# MainMCU.net
KiCad netlist of a schematic drawn in Altium Designer
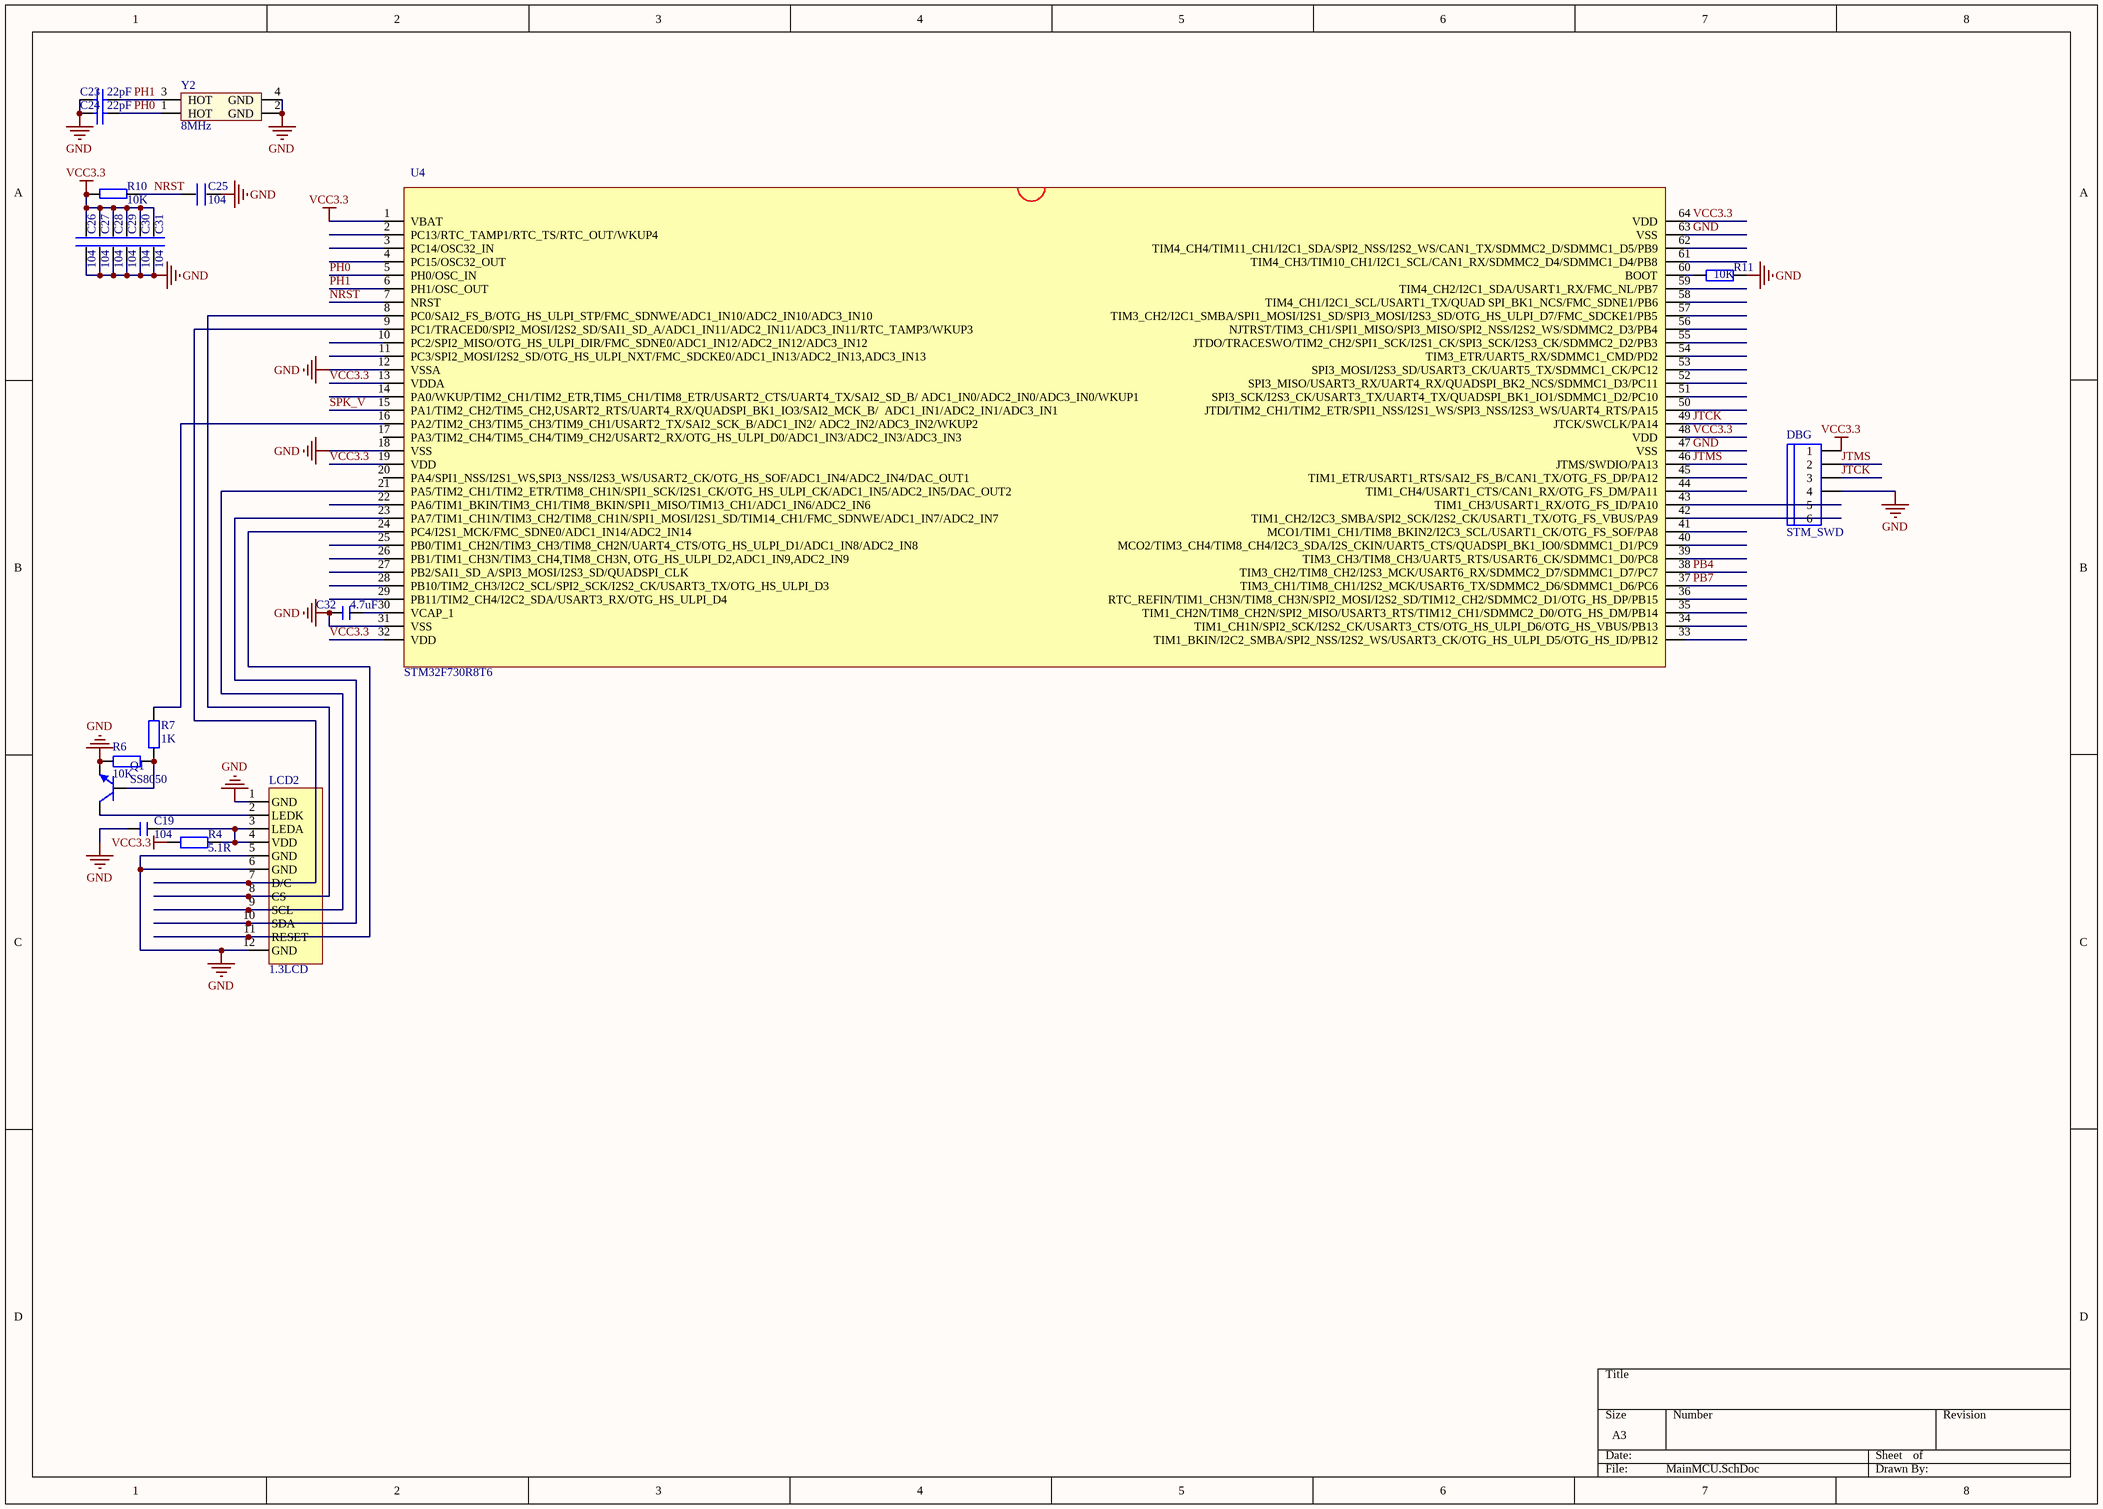
[diagram p0: MainMCU.SchDoc]

(export (version "E")
  (design (tool "Eeschema 10.0.6"))
  (components
    (comp (ref "C19")
      (value "104")
      (footprint "C 0603_L")
      (description "无极性电容")
      (fields (field (name "版权归属") "正点原子"))
      (libsource (lib "正点原子封装库V1.0") (part "C"))
    )
    (comp (ref "C23") (value "22pF") (footprint "C 0603_L") (libsource (lib "L476") (part "CAP")))
    (comp (ref "C24") (value "22pF") (footprint "C 0603_L") (libsource (lib "L476") (part "CAP")))
    (comp (ref "C25")
      (value "104")
      (footprint "C 0603_L")
      (libsource (lib "IMX6UL_ALPHA(底板)_V2.0") (part "C"))
    )
    (comp (ref "C26")
      (value "104")
      (footprint "C 0603_L")
      (libsource (lib "IMX6UL_ALPHA(底板)_V2.0") (part "C"))
    )
    (comp (ref "C27")
      (value "104")
      (footprint "C 0603_L")
      (libsource (lib "IMX6UL_ALPHA(底板)_V2.0") (part "C"))
    )
    (comp (ref "C28")
      (value "104")
      (footprint "C 0603_L")
      (libsource (lib "IMX6UL_ALPHA(底板)_V2.0") (part "C"))
    )
    (comp (ref "C29")
      (value "104")
      (footprint "C 0603_L")
      (libsource (lib "IMX6UL_ALPHA(底板)_V2.0") (part "C"))
    )
    (comp (ref "C30")
      (value "104")
      (footprint "C 0603_L")
      (libsource (lib "IMX6UL_ALPHA(底板)_V2.0") (part "C"))
    )
    (comp (ref "C31")
      (value "104")
      (footprint "C 0603_L")
      (libsource (lib "IMX6UL_ALPHA(底板)_V2.0") (part "C"))
    )
    (comp (ref "C32")
      (value "4.7uF")
      (footprint "C 0603_L")
      (description "无极性贴片电容")
      (fields (field (name "版权归属") "源创客"))
      (libsource (lib "电阻-电容-电感") (part "C"))
    )
    (comp (ref "DBG")
      (value "STM_SWD")
      (footprint "SH1.0 S-W-6P")
      (libsource (lib "MiniFly ") (part "HEAD6"))
    )
    (comp (ref "LCD2")
      (value "1.3LCD")
      (footprint "TFT-N133-2424THBIG01")
      (description "TFTLCD,240*240,SPI")
      (libsource (lib "ATK-MD0130 V2.0") (part "TFTLCD-N133-2424THBIG01"))
    )
    (comp (ref "Q1")
      (value "SS8050")
      (footprint "SOT23-3L")
      (description "高频放大-NPN型")
      (fields (field (name "版权归属") "正点原子"))
      (libsource (lib "正点原子封装库V1.0") (part "8050-SMD"))
    )
    (comp (ref "R4")
      (value "5.1R")
      (footprint "R 0805_L")
      (description "贴片电阻")
      (libsource (lib "LovelessingSch") (part "R"))
    )
    (comp (ref "R6")
      (value "10K")
      (footprint "R 0603_L")
      (description "贴片电阻")
      (libsource (lib "LovelessingSch") (part "R"))
    )
    (comp (ref "R7")
      (value "1K")
      (footprint "R 0603_L")
      (description "贴片电阻")
      (libsource (lib "LovelessingSch") (part "R"))
    )
    (comp (ref "R10")
      (value "10K")
      (footprint "R 0603_L")
      (libsource (lib "IMX6UL_ALPHA(底板)_V2.0") (part "R"))
    )
    (comp (ref "R11")
      (value "10K")
      (footprint "R 0603_L")
      (description "贴片电阻")
      (fields (field (name "版权归属") "源创客"))
      (libsource (lib "电阻-电容-电感") (part "R"))
    )
    (comp (ref "U4")
      (value "STM32F730R8T6")
      (footprint "LQFP64 10x10_L")
      (description "STM32 M7内核")
      (libsource (lib "fantasylib") (part "STM32F730R8T6"))
    )
    (comp (ref "Y2")
      (value "8MHz")
      (footprint "OSC 3225-4P")
      (description "晶振25MHz")
      (fields (field (name "PUBLISHER") "Altium Limited"))
      (libsource (lib "LovelessingSch") (part "Y-3225-4P"))
    )
  )
  (nets
    (net (code "1") (name "/JTCK") (class "Default")
      (node (ref "DBG") (pin "3") (pinfunction "3_3") (pintype "passive"))
      (node (ref "U4") (pin "49") (pinfunction "JTCK/SWCLK/PA14_49") (pintype "passive"))
    )
    (net (code "2") (name "/JTMS") (class "Default")
      (node (ref "DBG") (pin "2") (pinfunction "2_2") (pintype "passive"))
      (node (ref "U4") (pin "46") (pinfunction "JTMS/SWDIO/PA13_46") (pintype "passive"))
    )
    (net (code "3") (name "/NRST") (class "Default")
      (node (ref "C25") (pin "2") (pintype "passive"))
      (node (ref "R10") (pin "1") (pintype "passive"))
      (node (ref "U4") (pin "7") (pinfunction "NRST_7") (pintype "passive"))
    )
    (net (code "4") (name "/PB4") (class "Default")
      (node (ref "U4") (pin "38") (pinfunction "TIM3_CH2/TIM8_CH2/I2S3_MCK/USART6_RX/SDMMC2_D7/SDMMC1_D7/PC7_38") (pintype "passive"))
    )
    (net (code "5") (name "/PB7") (class "Default")
      (node (ref "U4") (pin "37") (pinfunction "TIM3_CH1/TIM8_CH1/I2S2_MCK/USART6_TX/SDMMC2_D6/SDMMC1_D6/PC6_37") (pintype "passive"))
    )
    (net (code "6") (name "/PH0") (class "Default")
      (node (ref "C24") (pin "1") (pinfunction "1_1") (pintype "passive"))
      (node (ref "U4") (pin "5") (pinfunction "PH0/OSC_IN_5") (pintype "passive"))
      (node (ref "Y2") (pin "1") (pinfunction "HOT_1") (pintype "passive"))
    )
    (net (code "7") (name "/PH1") (class "Default")
      (node (ref "C23") (pin "1") (pinfunction "1_1") (pintype "passive"))
      (node (ref "U4") (pin "6") (pinfunction "PH1/OSC_OUT_6") (pintype "passive"))
      (node (ref "Y2") (pin "3") (pinfunction "HOT_3") (pintype "passive"))
    )
    (net (code "8") (name "/SPK_V") (class "Default")
      (node (ref "U4") (pin "15") (pinfunction "PA1/TIM2_CH2/TIM5_CH2,USART2_RTS/UART4_RX/QUADSPI_BK1_IO3/SAI2_MCK_B/__ADC1_IN1/ADC2_IN1/ADC3_IN1_15") (pintype "passive"))
    )
    (net (code "9") (name "GND") (class "Default")
      (node (ref "C19") (pin "2") (pinfunction "2_2") (pintype "passive"))
      (node (ref "C23") (pin "2") (pinfunction "2_2") (pintype "passive"))
      (node (ref "C24") (pin "2") (pinfunction "2_2") (pintype "passive"))
      (node (ref "C25") (pin "1") (pintype "passive"))
      (node (ref "C26") (pin "2") (pintype "passive"))
      (node (ref "C27") (pin "2") (pintype "passive"))
      (node (ref "C28") (pin "2") (pintype "passive"))
      (node (ref "C29") (pin "2") (pintype "passive"))
      (node (ref "C30") (pin "2") (pintype "passive"))
      (node (ref "C31") (pin "2") (pintype "passive"))
      (node (ref "C32") (pin "1") (pinfunction "1_1") (pintype "passive"))
      (node (ref "DBG") (pin "4") (pinfunction "4_4") (pintype "passive"))
      (node (ref "LCD2") (pin "1") (pinfunction "GND_1") (pintype "passive"))
      (node (ref "LCD2") (pin "12") (pinfunction "GND_12") (pintype "passive"))
      (node (ref "LCD2") (pin "5") (pinfunction "GND_5") (pintype "passive"))
      (node (ref "LCD2") (pin "6") (pinfunction "GND_6") (pintype "passive"))
      (node (ref "Q1") (pin "2") (pinfunction "E_2") (pintype "passive"))
      (node (ref "R11") (pin "1") (pinfunction "1_1") (pintype "passive"))
      (node (ref "R6") (pin "2") (pinfunction "2_2") (pintype "passive"))
      (node (ref "U4") (pin "12") (pinfunction "VSSA_12") (pintype "passive"))
      (node (ref "U4") (pin "18") (pinfunction "VSS_18") (pintype "passive"))
      (node (ref "U4") (pin "31") (pinfunction "VSS_31") (pintype "passive"))
      (node (ref "U4") (pin "47") (pinfunction "VSS_47") (pintype "passive"))
      (node (ref "U4") (pin "63") (pinfunction "VSS_63") (pintype "passive"))
      (node (ref "Y2") (pin "2") (pinfunction "GND_2") (pintype "passive"))
      (node (ref "Y2") (pin "4") (pinfunction "GND_4") (pintype "passive"))
    )
    (net (code "10") (name "Net-(LCD2-CS)") (class "Default")
      (node (ref "LCD2") (pin "8") (pinfunction "CS_8") (pintype "passive"))
      (node (ref "U4") (pin "8") (pinfunction "PC0/SAI2_FS_B/OTG_HS_ULPI_STP/FMC_SDNWE/ADC1_IN10/ADC2_IN10/ADC3_IN10_8") (pintype "passive"))
    )
    (net (code "11") (name "Net-(LCD2-D{slash}C)") (class "Default")
      (node (ref "LCD2") (pin "7") (pinfunction "D/C_7") (pintype "passive"))
      (node (ref "U4") (pin "9") (pinfunction "PC1/TRACED0/SPI2_MOSI/I2S2_SD/SAI1_SD_A/ADC1_IN11/ADC2_IN11/ADC3_IN11/RTC_TAMP3/WKUP3_9") (pintype "passive"))
    )
    (net (code "12") (name "Net-(LCD2-LEDA)") (class "Default")
      (node (ref "C19") (pin "1") (pinfunction "1_1") (pintype "passive"))
      (node (ref "LCD2") (pin "3") (pinfunction "LEDA_3") (pintype "passive"))
      (node (ref "LCD2") (pin "4") (pinfunction "VDD_4") (pintype "passive"))
      (node (ref "R4") (pin "2") (pinfunction "2_2") (pintype "passive"))
    )
    (net (code "13") (name "Net-(LCD2-LEDK)") (class "Default")
      (node (ref "LCD2") (pin "2") (pinfunction "LEDK_2") (pintype "passive"))
      (node (ref "Q1") (pin "3") (pinfunction "C_3") (pintype "passive"))
    )
    (net (code "14") (name "Net-(LCD2-RESET)") (class "Default")
      (node (ref "LCD2") (pin "11") (pinfunction "RESET_11") (pintype "passive"))
      (node (ref "U4") (pin "24") (pinfunction "PC4/I2S1_MCK/FMC_SDNE0/ADC1_IN14/ADC2_IN14_24") (pintype "passive"))
    )
    (net (code "15") (name "Net-(LCD2-SCL)") (class "Default")
      (node (ref "LCD2") (pin "9") (pinfunction "SCL_9") (pintype "passive"))
      (node (ref "U4") (pin "21") (pinfunction "PA5/TIM2_CH1/TIM2_ETR/TIM8_CH1N/SPI1_SCK/I2S1_CK/OTG_HS_ULPI_CK/ADC1_IN5/ADC2_IN5/DAC_OUT2_21") (pintype "passive"))
    )
    (net (code "16") (name "Net-(LCD2-SDA)") (class "Default")
      (node (ref "LCD2") (pin "10") (pinfunction "SDA_10") (pintype "passive"))
      (node (ref "U4") (pin "23") (pinfunction "PA7/TIM1_CH1N/TIM3_CH2/TIM8_CH1N/SPI1_MOSI/I2S1_SD/TIM14_CH1/FMC_SDNWE/ADC1_IN7/ADC2_IN7_23") (pintype "passive"))
    )
    (net (code "17") (name "Net-(Q1-B)") (class "Default")
      (node (ref "Q1") (pin "1") (pinfunction "B_1") (pintype "passive"))
      (node (ref "R6") (pin "1") (pinfunction "1_1") (pintype "passive"))
      (node (ref "R7") (pin "2") (pinfunction "2_2") (pintype "passive"))
    )
    (net (code "18") (name "Net-(U4-BOOT)") (class "Default")
      (node (ref "R11") (pin "2") (pinfunction "2_2") (pintype "passive"))
      (node (ref "U4") (pin "60") (pinfunction "BOOT_60") (pintype "passive"))
    )
    (net (code "19") (name "Net-(U4-PA2{slash}TIM2_CH3{slash}TIM5_CH3{slash}TIM9_CH1{slash}USART2_TX{slash}SAI2_SCK_B{slash}ADC1_IN2{slash}_ADC2_IN2{slash}ADC3_IN2{slash}WKUP2)") (class "Default")
      (node (ref "R7") (pin "1") (pinfunction "1_1") (pintype "passive"))
      (node (ref "U4") (pin "16") (pinfunction "PA2/TIM2_CH3/TIM5_CH3/TIM9_CH1/USART2_TX/SAI2_SCK_B/ADC1_IN2/_ADC2_IN2/ADC3_IN2/WKUP2_16") (pintype "passive"))
    )
    (net (code "20") (name "Net-(U4-TIM1_CH2{slash}I2C3_SMBA{slash}SPI2_SCK{slash}I2S2_CK{slash}USART1_TX{slash}OTG_FS_VBUS{slash}PA9)") (class "Default")
      (node (ref "DBG") (pin "6") (pinfunction "6_6") (pintype "passive"))
      (node (ref "U4") (pin "42") (pinfunction "TIM1_CH2/I2C3_SMBA/SPI2_SCK/I2S2_CK/USART1_TX/OTG_FS_VBUS/PA9_42") (pintype "passive"))
    )
    (net (code "21") (name "Net-(U4-TIM1_CH3{slash}USART1_RX{slash}OTG_FS_ID{slash}PA10)") (class "Default")
      (node (ref "DBG") (pin "5") (pinfunction "5_5") (pintype "passive"))
      (node (ref "U4") (pin "43") (pinfunction "TIM1_CH3/USART1_RX/OTG_FS_ID/PA10_43") (pintype "passive"))
    )
    (net (code "22") (name "Net-(U4-VCAP_1)") (class "Default")
      (node (ref "C32") (pin "2") (pinfunction "2_2") (pintype "passive"))
      (node (ref "U4") (pin "30") (pinfunction "VCAP_1_30") (pintype "passive"))
    )
    (net (code "23") (name "VCC3.3") (class "Default")
      (node (ref "C26") (pin "1") (pintype "passive"))
      (node (ref "C27") (pin "1") (pintype "passive"))
      (node (ref "C28") (pin "1") (pintype "passive"))
      (node (ref "C29") (pin "1") (pintype "passive"))
      (node (ref "C30") (pin "1") (pintype "passive"))
      (node (ref "C31") (pin "1") (pintype "passive"))
      (node (ref "DBG") (pin "1") (pinfunction "1_1") (pintype "passive"))
      (node (ref "R10") (pin "2") (pintype "passive"))
      (node (ref "R4") (pin "1") (pinfunction "1_1") (pintype "passive"))
      (node (ref "U4") (pin "1") (pinfunction "VBAT_1") (pintype "passive"))
      (node (ref "U4") (pin "13") (pinfunction "VDDA_13") (pintype "passive"))
      (node (ref "U4") (pin "19") (pinfunction "VDD_19") (pintype "passive"))
      (node (ref "U4") (pin "32") (pinfunction "VDD_32") (pintype "passive"))
      (node (ref "U4") (pin "48") (pinfunction "VDD_48") (pintype "passive"))
      (node (ref "U4") (pin "64") (pinfunction "VDD_64") (pintype "passive"))
    )
    (net (code "24") (name "unconnected-(U4-JTDI{slash}TIM2_CH1{slash}TIM2_ETR{slash}SPI1_NSS{slash}I2S1_WS{slash}SPI3_NSS{slash}I2S3_WS{slash}UART4_RTS{slash}PA15-Pad50)") (class "Default")
      (node (ref "U4") (pin "50") (pinfunction "JTDI/TIM2_CH1/TIM2_ETR/SPI1_NSS/I2S1_WS/SPI3_NSS/I2S3_WS/UART4_RTS/PA15_50") (pintype "passive"))
    )
    (net (code "25") (name "unconnected-(U4-JTDO{slash}TRACESWO{slash}TIM2_CH2{slash}SPI1_SCK{slash}I2S1_CK{slash}SPI3_SCK{slash}I2S3_CK{slash}SDMMC2_D2{slash}PB3-Pad55)") (class "Default")
      (node (ref "U4") (pin "55") (pinfunction "JTDO/TRACESWO/TIM2_CH2/SPI1_SCK/I2S1_CK/SPI3_SCK/I2S3_CK/SDMMC2_D2/PB3_55") (pintype "passive"))
    )
    (net (code "26") (name "unconnected-(U4-MCO1{slash}TIM1_CH1{slash}TIM8_BKIN2{slash}I2C3_SCL{slash}USART1_CK{slash}OTG_FS_SOF{slash}PA8-Pad41)") (class "Default")
      (node (ref "U4") (pin "41") (pinfunction "MCO1/TIM1_CH1/TIM8_BKIN2/I2C3_SCL/USART1_CK/OTG_FS_SOF/PA8_41") (pintype "passive"))
    )
    (net (code "27") (name "unconnected-(U4-MCO2{slash}TIM3_CH4{slash}TIM8_CH4{slash}I2C3_SDA{slash}I2S_CKIN{slash}UART5_CTS{slash}QUADSPI_BK1_IO0{slash}SDMMC1_D1{slash}PC9-Pad40)") (class "Default")
      (node (ref "U4") (pin "40") (pinfunction "MCO2/TIM3_CH4/TIM8_CH4/I2C3_SDA/I2S_CKIN/UART5_CTS/QUADSPI_BK1_IO0/SDMMC1_D1/PC9_40") (pintype "passive"))
    )
    (net (code "28") (name "unconnected-(U4-NJTRST{slash}TIM3_CH1{slash}SPI1_MISO{slash}SPI3_MISO{slash}SPI2_NSS{slash}I2S2_WS{slash}SDMMC2_D3{slash}PB4-Pad56)") (class "Default")
      (node (ref "U4") (pin "56") (pinfunction "NJTRST/TIM3_CH1/SPI1_MISO/SPI3_MISO/SPI2_NSS/I2S2_WS/SDMMC2_D3/PB4_56") (pintype "passive"))
    )
    (net (code "29") (name "unconnected-(U4-PA0{slash}WKUP{slash}TIM2_CH1{slash}TIM2_ETR,TIM5_CH1{slash}TIM8_ETR{slash}USART2_CTS{slash}UART4_TX{slash}SAI2_SD_B{slash}_ADC1_IN0{slash}ADC2_IN0{slash}ADC3_IN0{slash}WKUP1-Pad14)") (class "Default")
      (node (ref "U4") (pin "14") (pinfunction "PA0/WKUP/TIM2_CH1/TIM2_ETR,TIM5_CH1/TIM8_ETR/USART2_CTS/UART4_TX/SAI2_SD_B/_ADC1_IN0/ADC2_IN0/ADC3_IN0/WKUP1_14") (pintype "passive"))
    )
    (net (code "30") (name "unconnected-(U4-PA3{slash}TIM2_CH4{slash}TIM5_CH4{slash}TIM9_CH2{slash}USART2_RX{slash}OTG_HS_ULPI_D0{slash}ADC1_IN3{slash}ADC2_IN3{slash}ADC3_IN3-Pad17)") (class "Default")
      (node (ref "U4") (pin "17") (pinfunction "PA3/TIM2_CH4/TIM5_CH4/TIM9_CH2/USART2_RX/OTG_HS_ULPI_D0/ADC1_IN3/ADC2_IN3/ADC3_IN3_17") (pintype "passive"))
    )
    (net (code "31") (name "unconnected-(U4-PA4{slash}SPI1_NSS{slash}I2S1_WS,SPI3_NSS{slash}I2S3_WS{slash}USART2_CK{slash}OTG_HS_SOF{slash}ADC1_IN4{slash}ADC2_IN4{slash}DAC_OUT1-Pad20)") (class "Default")
      (node (ref "U4") (pin "20") (pinfunction "PA4/SPI1_NSS/I2S1_WS,SPI3_NSS/I2S3_WS/USART2_CK/OTG_HS_SOF/ADC1_IN4/ADC2_IN4/DAC_OUT1_20") (pintype "passive"))
    )
    (net (code "32") (name "unconnected-(U4-PA6{slash}TIM1_BKIN{slash}TIM3_CH1{slash}TIM8_BKIN{slash}SPI1_MISO{slash}TIM13_CH1{slash}ADC1_IN6{slash}ADC2_IN6-Pad22)") (class "Default")
      (node (ref "U4") (pin "22") (pinfunction "PA6/TIM1_BKIN/TIM3_CH1/TIM8_BKIN/SPI1_MISO/TIM13_CH1/ADC1_IN6/ADC2_IN6_22") (pintype "passive"))
    )
    (net (code "33") (name "unconnected-(U4-PB0{slash}TIM1_CH2N{slash}TIM3_CH3{slash}TIM8_CH2N{slash}UART4_CTS{slash}OTG_HS_ULPI_D1{slash}ADC1_IN8{slash}ADC2_IN8-Pad25)") (class "Default")
      (node (ref "U4") (pin "25") (pinfunction "PB0/TIM1_CH2N/TIM3_CH3/TIM8_CH2N/UART4_CTS/OTG_HS_ULPI_D1/ADC1_IN8/ADC2_IN8_25") (pintype "passive"))
    )
    (net (code "34") (name "unconnected-(U4-PB1{slash}TIM1_CH3N{slash}TIM3_CH4,TIM8_CH3N,_OTG_HS_ULPI_D2,ADC1_IN9,ADC2_IN9-Pad26)") (class "Default")
      (node (ref "U4") (pin "26") (pinfunction "PB1/TIM1_CH3N/TIM3_CH4,TIM8_CH3N,_OTG_HS_ULPI_D2,ADC1_IN9,ADC2_IN9_26") (pintype "passive"))
    )
    (net (code "35") (name "unconnected-(U4-PB2{slash}SAI1_SD_A{slash}SPI3_MOSI{slash}I2S3_SD{slash}QUADSPI_CLK-Pad27)") (class "Default")
      (node (ref "U4") (pin "27") (pinfunction "PB2/SAI1_SD_A/SPI3_MOSI/I2S3_SD/QUADSPI_CLK_27") (pintype "passive"))
    )
    (net (code "36") (name "unconnected-(U4-PB10{slash}TIM2_CH3{slash}I2C2_SCL{slash}SPI2_SCK{slash}I2S2_CK{slash}USART3_TX{slash}OTG_HS_ULPI_D3-Pad28)") (class "Default")
      (node (ref "U4") (pin "28") (pinfunction "PB10/TIM2_CH3/I2C2_SCL/SPI2_SCK/I2S2_CK/USART3_TX/OTG_HS_ULPI_D3_28") (pintype "passive"))
    )
    (net (code "37") (name "unconnected-(U4-PB11{slash}TIM2_CH4{slash}I2C2_SDA{slash}USART3_RX{slash}OTG_HS_ULPI_D4-Pad29)") (class "Default")
      (node (ref "U4") (pin "29") (pinfunction "PB11/TIM2_CH4/I2C2_SDA/USART3_RX/OTG_HS_ULPI_D4_29") (pintype "passive"))
    )
    (net (code "38") (name "unconnected-(U4-PC2{slash}SPI2_MISO{slash}OTG_HS_ULPI_DIR{slash}FMC_SDNE0{slash}ADC1_IN12{slash}ADC2_IN12{slash}ADC3_IN12-Pad10)") (class "Default")
      (node (ref "U4") (pin "10") (pinfunction "PC2/SPI2_MISO/OTG_HS_ULPI_DIR/FMC_SDNE0/ADC1_IN12/ADC2_IN12/ADC3_IN12_10") (pintype "passive"))
    )
    (net (code "39") (name "unconnected-(U4-PC3{slash}SPI2_MOSI{slash}I2S2_SD{slash}OTG_HS_ULPI_NXT{slash}FMC_SDCKE0{slash}ADC1_IN13{slash}ADC2_IN13,ADC3_IN13-Pad11)") (class "Default")
      (node (ref "U4") (pin "11") (pinfunction "PC3/SPI2_MOSI/I2S2_SD/OTG_HS_ULPI_NXT/FMC_SDCKE0/ADC1_IN13/ADC2_IN13,ADC3_IN13_11") (pintype "passive"))
    )
    (net (code "40") (name "unconnected-(U4-PC13{slash}RTC_TAMP1{slash}RTC_TS{slash}RTC_OUT{slash}WKUP4-Pad2)") (class "Default")
      (node (ref "U4") (pin "2") (pinfunction "PC13/RTC_TAMP1/RTC_TS/RTC_OUT/WKUP4_2") (pintype "passive"))
    )
    (net (code "41") (name "unconnected-(U4-PC14{slash}OSC32_IN-Pad3)") (class "Default")
      (node (ref "U4") (pin "3") (pinfunction "PC14/OSC32_IN_3") (pintype "passive"))
    )
    (net (code "42") (name "unconnected-(U4-PC15{slash}OSC32_OUT-Pad4)") (class "Default")
      (node (ref "U4") (pin "4") (pinfunction "PC15/OSC32_OUT_4") (pintype "passive"))
    )
    (net (code "43") (name "unconnected-(U4-RTC_REFIN{slash}TIM1_CH3N{slash}TIM8_CH3N{slash}SPI2_MOSI{slash}I2S2_SD{slash}TIM12_CH2{slash}SDMMC2_D1{slash}OTG_HS_DP{slash}PB15-Pad36)") (class "Default")
      (node (ref "U4") (pin "36") (pinfunction "RTC_REFIN/TIM1_CH3N/TIM8_CH3N/SPI2_MOSI/I2S2_SD/TIM12_CH2/SDMMC2_D1/OTG_HS_DP/PB15_36") (pintype "passive"))
    )
    (net (code "44") (name "unconnected-(U4-SPI3_MISO{slash}USART3_RX{slash}UART4_RX{slash}QUADSPI_BK2_NCS{slash}SDMMC1_D3{slash}PC11-Pad52)") (class "Default")
      (node (ref "U4") (pin "52") (pinfunction "SPI3_MISO/USART3_RX/UART4_RX/QUADSPI_BK2_NCS/SDMMC1_D3/PC11_52") (pintype "passive"))
    )
    (net (code "45") (name "unconnected-(U4-SPI3_MOSI{slash}I2S3_SD{slash}USART3_CK{slash}UART5_TX{slash}SDMMC1_CK{slash}PC12-Pad53)") (class "Default")
      (node (ref "U4") (pin "53") (pinfunction "SPI3_MOSI/I2S3_SD/USART3_CK/UART5_TX/SDMMC1_CK/PC12_53") (pintype "passive"))
    )
    (net (code "46") (name "unconnected-(U4-SPI3_SCK{slash}I2S3_CK{slash}USART3_TX{slash}UART4_TX{slash}QUADSPI_BK1_IO1{slash}SDMMC1_D2{slash}PC10-Pad51)") (class "Default")
      (node (ref "U4") (pin "51") (pinfunction "SPI3_SCK/I2S3_CK/USART3_TX/UART4_TX/QUADSPI_BK1_IO1/SDMMC1_D2/PC10_51") (pintype "passive"))
    )
    (net (code "47") (name "unconnected-(U4-TIM1_BKIN{slash}I2C2_SMBA{slash}SPI2_NSS{slash}I2S2_WS{slash}USART3_CK{slash}OTG_HS_ULPI_D5{slash}OTG_HS_ID{slash}PB12-Pad33)") (class "Default")
      (node (ref "U4") (pin "33") (pinfunction "TIM1_BKIN/I2C2_SMBA/SPI2_NSS/I2S2_WS/USART3_CK/OTG_HS_ULPI_D5/OTG_HS_ID/PB12_33") (pintype "passive"))
    )
    (net (code "48") (name "unconnected-(U4-TIM1_CH1N{slash}SPI2_SCK{slash}I2S2_CK{slash}USART3_CTS{slash}OTG_HS_ULPI_D6{slash}OTG_HS_VBUS{slash}PB13-Pad34)") (class "Default")
      (node (ref "U4") (pin "34") (pinfunction "TIM1_CH1N/SPI2_SCK/I2S2_CK/USART3_CTS/OTG_HS_ULPI_D6/OTG_HS_VBUS/PB13_34") (pintype "passive"))
    )
    (net (code "49") (name "unconnected-(U4-TIM1_CH2N{slash}TIM8_CH2N{slash}SPI2_MISO{slash}USART3_RTS{slash}TIM12_CH1{slash}SDMMC2_D0{slash}OTG_HS_DM{slash}PB14-Pad35)") (class "Default")
      (node (ref "U4") (pin "35") (pinfunction "TIM1_CH2N/TIM8_CH2N/SPI2_MISO/USART3_RTS/TIM12_CH1/SDMMC2_D0/OTG_HS_DM/PB14_35") (pintype "passive"))
    )
    (net (code "50") (name "unconnected-(U4-TIM1_CH4{slash}USART1_CTS{slash}CAN1_RX{slash}OTG_FS_DM{slash}PA11-Pad44)") (class "Default")
      (node (ref "U4") (pin "44") (pinfunction "TIM1_CH4/USART1_CTS/CAN1_RX/OTG_FS_DM/PA11_44") (pintype "passive"))
    )
    (net (code "51") (name "unconnected-(U4-TIM1_ETR{slash}USART1_RTS{slash}SAI2_FS_B{slash}CAN1_TX{slash}OTG_FS_DP{slash}PA12-Pad45)") (class "Default")
      (node (ref "U4") (pin "45") (pinfunction "TIM1_ETR/USART1_RTS/SAI2_FS_B/CAN1_TX/OTG_FS_DP/PA12_45") (pintype "passive"))
    )
    (net (code "52") (name "unconnected-(U4-TIM3_CH2{slash}I2C1_SMBA{slash}SPI1_MOSI{slash}I2S1_SD{slash}SPI3_MOSI{slash}I2S3_SD{slash}OTG_HS_ULPI_D7{slash}FMC_SDCKE1{slash}PB5-Pad57)") (class "Default")
      (node (ref "U4") (pin "57") (pinfunction "TIM3_CH2/I2C1_SMBA/SPI1_MOSI/I2S1_SD/SPI3_MOSI/I2S3_SD/OTG_HS_ULPI_D7/FMC_SDCKE1/PB5_57") (pintype "passive"))
    )
    (net (code "53") (name "unconnected-(U4-TIM3_CH3{slash}TIM8_CH3{slash}UART5_RTS{slash}USART6_CK{slash}SDMMC1_D0{slash}PC8-Pad39)") (class "Default")
      (node (ref "U4") (pin "39") (pinfunction "TIM3_CH3/TIM8_CH3/UART5_RTS/USART6_CK/SDMMC1_D0/PC8_39") (pintype "passive"))
    )
    (net (code "54") (name "unconnected-(U4-TIM3_ETR{slash}UART5_RX{slash}SDMMC1_CMD{slash}PD2-Pad54)") (class "Default")
      (node (ref "U4") (pin "54") (pinfunction "TIM3_ETR/UART5_RX/SDMMC1_CMD/PD2_54") (pintype "passive"))
    )
    (net (code "55") (name "unconnected-(U4-TIM4_CH1{slash}I2C1_SCL{slash}USART1_TX{slash}QUAD_SPI_BK1_NCS{slash}FMC_SDNE1{slash}PB6-Pad58)") (class "Default")
      (node (ref "U4") (pin "58") (pinfunction "TIM4_CH1/I2C1_SCL/USART1_TX/QUAD_SPI_BK1_NCS/FMC_SDNE1/PB6_58") (pintype "passive"))
    )
    (net (code "56") (name "unconnected-(U4-TIM4_CH2{slash}I2C1_SDA{slash}USART1_RX{slash}FMC_NL{slash}PB7-Pad59)") (class "Default")
      (node (ref "U4") (pin "59") (pinfunction "TIM4_CH2/I2C1_SDA/USART1_RX/FMC_NL/PB7_59") (pintype "passive"))
    )
    (net (code "57") (name "unconnected-(U4-TIM4_CH3{slash}TIM10_CH1{slash}I2C1_SCL{slash}CAN1_RX{slash}SDMMC2_D4{slash}SDMMC1_D4{slash}PB8-Pad61)") (class "Default")
      (node (ref "U4") (pin "61") (pinfunction "TIM4_CH3/TIM10_CH1/I2C1_SCL/CAN1_RX/SDMMC2_D4/SDMMC1_D4/PB8_61") (pintype "passive"))
    )
    (net (code "58") (name "unconnected-(U4-TIM4_CH4{slash}TIM11_CH1{slash}I2C1_SDA{slash}SPI2_NSS{slash}I2S2_WS{slash}CAN1_TX{slash}SDMMC2_D{slash}SDMMC1_D5{slash}PB9-Pad62)") (class "Default")
      (node (ref "U4") (pin "62") (pinfunction "TIM4_CH4/TIM11_CH1/I2C1_SDA/SPI2_NSS/I2S2_WS/CAN1_TX/SDMMC2_D/SDMMC1_D5/PB9_62") (pintype "passive"))
    )
  )
)
